# Buck_Schematic.net
KiCad netlist of a schematic drawn in Altium Designer
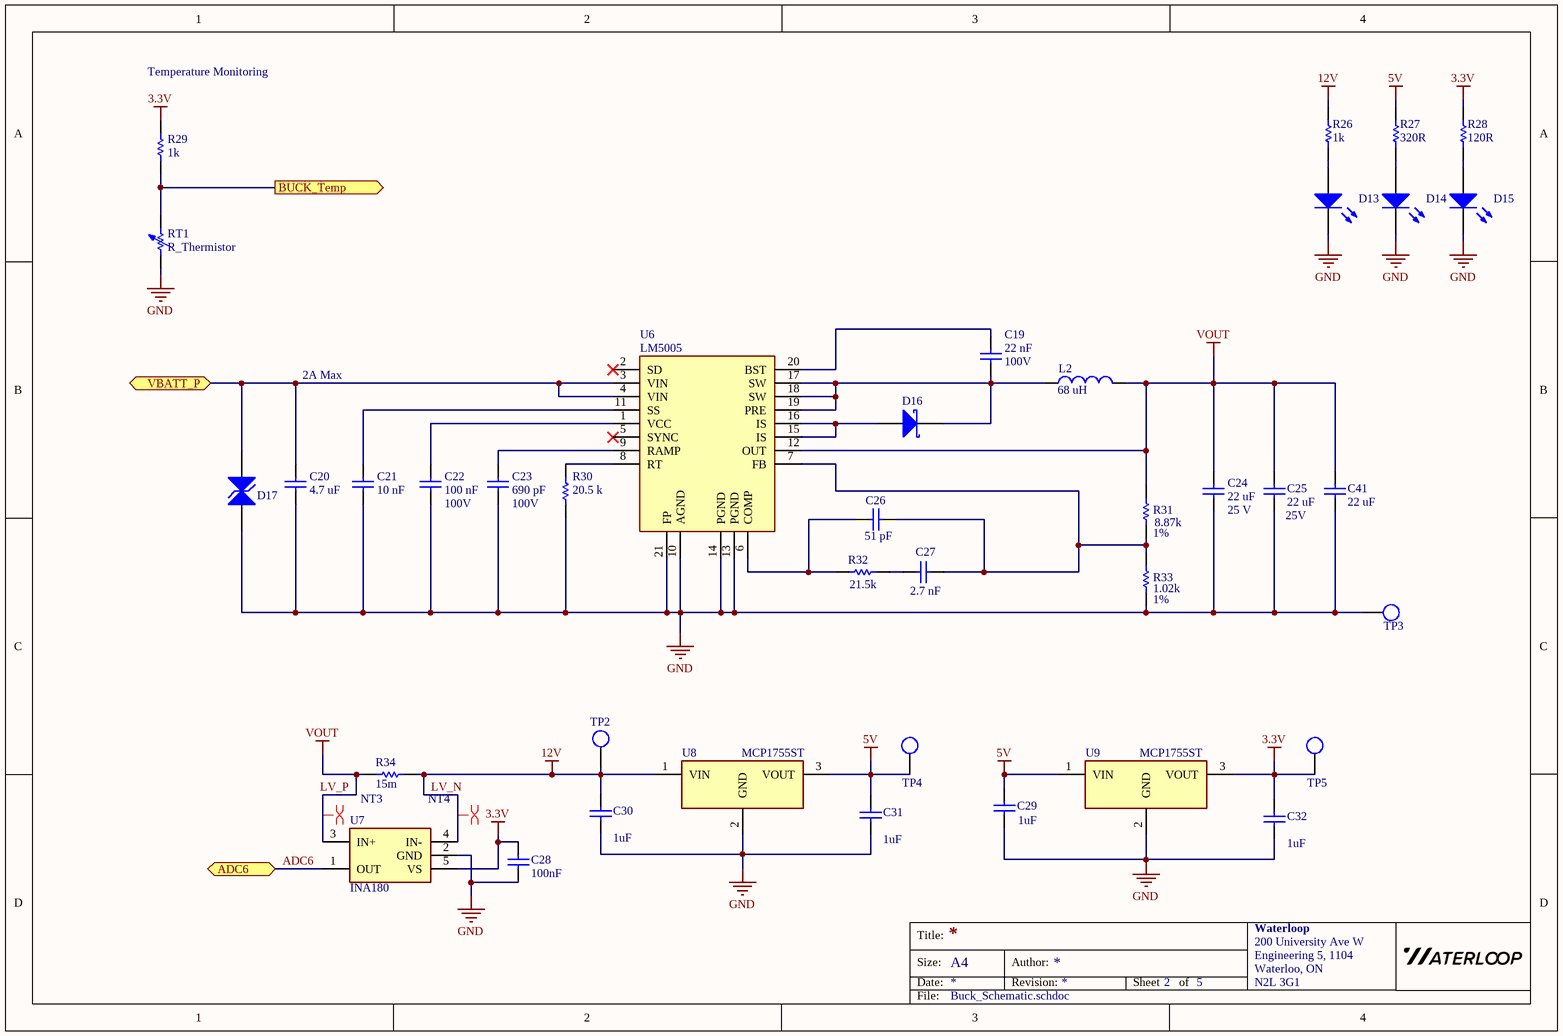
[diagram p0: Buck_Schematic.schdoc]

(export (version "E")
  (design (tool "Eeschema 10.0.6"))
  (components
    (comp (ref "C19")
      (value "22 nF")
      (footprint "0805 - Capacitor")
      (description "CC0805MRX7R0BB223, 0.022 µF± 20% 100V Ceramic Capacitor X7R 0805 (2012 Metric)")
      (fields
        (field (name "MANUFACTURER") "YAGEO")
        (field (name "MANUFACTURER PART NUMBER") "CC0805MRX7R0BB223")
      )
      (libsource (lib "General") (part "Capacitor - Nonpolarized"))
    )
    (comp (ref "C20")
      (value "4.7 uF")
      (footprint "1210 - Capacitor")
      (description "C3225X7S2A475M200AB, CAP CER 4.7UF 100V X7S 1210")
      (fields
        (field (name "MANUFACTURER") "TDK Corporation")
        (field (name "MANUFACTURER PART NUMBER") "C3225X7S2A475M200AB")
      )
      (libsource (lib "General") (part "Capacitor - Nonpolarized"))
    )
    (comp (ref "C21")
      (value "10 nF")
      (footprint "0805 - Capacitor")
      (description "CC0805KRX7R0BB103, 10000 pF ±10% 100V Ceramic Capacitor X7R 0805 (2012 Metric)")
      (fields
        (field (name "MANUFACTURER") "YAGEO")
        (field (name "MANUFACTURER PART NUMBER") "CC0805KRX7R0BB103")
      )
      (libsource (lib "General") (part "Capacitor - Nonpolarized"))
    )
    (comp (ref "C22")
      (value "100 nF")
      (footprint "0805 - Capacitor")
      (description "CC0805KKX7R0BB104, 0.1uF ± 10% 100V Ceramic Capacitor X7R 0805 (2012 Metric)")
      (fields
        (field (name "MANUFACTURER") "YAGEO")
        (field (name "MANUFACTURER PART NUMBER") "CC0805KKX7R0BB104")
      )
      (libsource (lib "General") (part "Capacitor - Nonpolarized"))
    )
    (comp (ref "C23")
      (value "690 pF")
      (footprint "0805 - Capacitor")
      (description "CC0805KRX7R0BB681, 680 pF ± 10% 100V Ceramic Capacitor X7R 0805 (2012 Metric)")
      (fields
        (field (name "MANUFACTURER") "YAGEO")
        (field (name "MANUFACTURER PART NUMBER") "CC0805KRX7R0BB681")
      )
      (libsource (lib "General") (part "Capacitor - Nonpolarized"))
    )
    (comp (ref "C24")
      (value "22 uF")
      (footprint "1210 - Capacitor")
      (description "CC0805ZKY5V6BB226, CAP CER 22UF 10V Y5V 0805")
      (fields
        (field (name "MANUFACTURER") "KYOCERA AVX")
        (field (name "MANUFACTURER PART NUMBER") "12103D226MAT2A")
      )
      (libsource (lib "General") (part "Capacitor - Nonpolarized"))
    )
    (comp (ref "C25")
      (value "22 uF")
      (footprint "1210 - Capacitor")
      (description "EEE-FK1A220R, CAP ALUM 22UF 20% 10V SMD")
      (fields
        (field (name "MANUFACTURER") "KYOCERA AVX")
        (field (name "MANUFACTURER PART NUMBER") "12103D226MAT2A")
      )
      (libsource (lib "General") (part "Capacitor - Nonpolarized"))
    )
    (comp (ref "C26")
      (value "51 pF")
      (footprint "0805 - Capacitor")
      (description "CL21C510JBANNNC,  51 pF ± 5% 50V Ceramic Capacitor C0G NP0 0805 (2012 Metric)")
      (fields
        (field (name "MANUFACTURER") "Samsung Electro-Mechanics")
        (field (name "MANUFACTURER PART NUMBER") "CL21C510JBANNNC")
      )
      (libsource (lib "General") (part "Capacitor - Nonpolarized"))
    )
    (comp (ref "C27")
      (value "2.7 nF")
      (footprint "0805 - Capacitor")
      (description "CC0805KRX7R9BB272, 2700 pF ±10% 50V Ceramic Capacitor X7R 0805 (2012 Metric)")
      (fields
        (field (name "MANUFACTURER") "YAGEO")
        (field (name "MANUFACTURER PART NUMBER") "CC0805KRX7R9BB272")
      )
      (libsource (lib "General") (part "Capacitor - Nonpolarized"))
    )
    (comp (ref "C28")
      (value "100nF")
      (footprint "0805 - Capacitor")
      (description "CC0805KRX7R9BB104, 0.1 µF  \r\n±10% 50V Ceramic Capacitor X7R 0805 (2012 Metric)")
      (fields
        (field (name "MANUFACTURER") "YAGEO")
        (field (name "MANUFACTURER PART NUMBER") "CC0805KRX7R9BB104")
      )
      (libsource (lib "General") (part "Capacitor - Nonpolarized"))
    )
    (comp (ref "C29")
      (value "1uF")
      (footprint "0805 - Capacitor")
      (description "Nonpolarized Capacitor")
      (fields
        (field (name "MANUFACTURER") "YAGEO")
        (field (name "MANUFACTURER PART NUMBER") "CC0805KKX5R8BB105")
      )
      (libsource (lib "General") (part "Capacitor - Nonpolarized"))
    )
    (comp (ref "C30")
      (value "1uF")
      (footprint "0805 - Capacitor")
      (description "Nonpolarized Capacitor")
      (fields
        (field (name "MANUFACTURER") "YAGEO")
        (field (name "MANUFACTURER PART NUMBER") "CC0805KKX5R8BB105")
      )
      (libsource (lib "General") (part "Capacitor - Nonpolarized"))
    )
    (comp (ref "C31")
      (value "1uF")
      (footprint "0805 - Capacitor")
      (description "Nonpolarized Capacitor")
      (fields
        (field (name "MANUFACTURER") "YAGEO")
        (field (name "MANUFACTURER PART NUMBER") "CC0805KKX5R8BB105")
      )
      (libsource (lib "General") (part "Capacitor - Nonpolarized"))
    )
    (comp (ref "C32")
      (value "1uF")
      (footprint "0805 - Capacitor")
      (description "Nonpolarized Capacitor")
      (fields
        (field (name "MANUFACTURER") "YAGEO")
        (field (name "MANUFACTURER PART NUMBER") "CC0805KKX5R8BB105")
      )
      (libsource (lib "General") (part "Capacitor - Nonpolarized"))
    )
    (comp (ref "C41")
      (value "22 uF")
      (footprint "1210 - Capacitor")
      (description "EEE-FK1A220R, CAP ALUM 22UF 20% 10V SMD")
      (fields
        (field (name "MANUFACTURER") "KYOCERA AVX")
        (field (name "MANUFACTURER PART NUMBER") "12103D226MAT2A")
      )
      (libsource (lib "General") (part "Capacitor - Nonpolarized"))
    )
    (comp (ref "D13")
      (value "LED")
      (footprint "0805 - Resistor")
      (description "150080SS75000, LED RED CLEAR 0805 SMD")
      (fields
        (field (name "MANUFACTURER PART NUMBER") "150080SS75000")
        (field (name "MANUFACTURER") "Würth Elektronik")
      )
      (libsource (lib "General") (part "LED"))
    )
    (comp (ref "D14")
      (value "LED")
      (footprint "0805 - Resistor")
      (description "150080SS75000, LED RED CLEAR 0805 SMD")
      (fields
        (field (name "MANUFACTURER PART NUMBER") "150080SS75000")
        (field (name "MANUFACTURER") "Würth Elektronik")
      )
      (libsource (lib "General") (part "LED"))
    )
    (comp (ref "D15")
      (value "LED")
      (footprint "0805 - Resistor")
      (description "150080SS75000, LED RED CLEAR 0805 SMD")
      (fields
        (field (name "MANUFACTURER PART NUMBER") "150080SS75000")
        (field (name "MANUFACTURER") "Würth Elektronik")
      )
      (libsource (lib "General") (part "LED"))
    )
    (comp (ref "D16")
      (value "Diode - Schottky")
      (footprint "SMA - DIODE")
      (description "SK220ATR, 200V 2A SMA")
      (fields
        (field (name "MANUFACTURER") "SMC Diode Solutions")
        (field (name "MANUFACTURER PART NUMBER") "SK220ATR")
      )
      (libsource (lib "General") (part "Diode - Schottky"))
    )
    (comp (ref "D17")
      (value "TVS")
      (footprint "SMB - DIODE")
      (description "TVS Diode")
      (fields (field (name "MANUFACTURER PART NUMBER") "824521601") (field (name "MANUFACTURER") "Wurth"))
      (libsource (lib "General") (part "TVS"))
    )
    (comp (ref "L2")
      (value "68 uH")
      (footprint "MSS1210 - INDUCTOR")
      (description "MSS1210-683MEB, 68 uH ± 20% 4.3 A Ferrite")
      (fields
        (field (name "MANUFACTURER PART NUMBER") "MSS1210-683MEB")
        (field (name "MANUFACTURER") "Coilcraft")
      )
      (libsource (lib "General") (part "Inductor"))
    )
    (comp (ref "NT3") (value "NetTie") (footprint "Net Tie") (libsource (lib "General") (part "Net Tie")))
    (comp (ref "NT4") (value "NetTie") (footprint "Net Tie") (libsource (lib "General") (part "Net Tie")))
    (comp (ref "R26")
      (value "1k")
      (footprint "0603 - Resistor")
      (description "RC0603FR-07510RL, RES 510 OHM 1% 1/10W 0603")
      (fields
        (field (name "MANUFACTURER PART NUMBER") "RC0603JR-071KL")
        (field (name "MANUFACTURER") "YAGEO")
      )
      (libsource (lib "General") (part "Resistor"))
    )
    (comp (ref "R27")
      (value "320R")
      (footprint "0603 - Resistor")
      (description "RC0603FR-07510RL, RES 510 OHM 1% 1/10W 0603")
      (fields
        (field (name "MANUFACTURER PART NUMBER") "RC0603FR-07330RL")
        (field (name "MANUFACTURER") "YAGEO")
      )
      (libsource (lib "General") (part "Resistor"))
    )
    (comp (ref "R28")
      (value "120R")
      (footprint "0603 - Resistor")
      (description "RC0603FR-07510RL, RES 510 OHM 1% 1/10W 0603")
      (fields
        (field (name "MANUFACTURER PART NUMBER") "RC0603FR-10120RL")
        (field (name "MANUFACTURER") "YAGEO")
      )
      (libsource (lib "General") (part "Resistor"))
    )
    (comp (ref "R29")
      (value "1k")
      (footprint "0603 - Resistor")
      (description "RC0603FR-071KL, 1 kOhms ±1% 0.1W Thick Film 0603 (1608 Metric)")
      (fields
        (field (name "MANUFACTURER PART NUMBER") "RC0603JR-071KL")
        (field (name "MANUFACTURER") "YAGEO")
      )
      (libsource (lib "General") (part "Resistor"))
    )
    (comp (ref "R30")
      (value "20.5 k")
      (footprint "0603 - Resistor")
      (description "CRCW060320K5FKEA, 20.5 kOhms ± 1%, 0.1W Thick Film 0603 (1608 Metric)")
      (fields
        (field (name "MANUFACTURER PART NUMBER") "CRCW060320K5FKEA")
        (field (name "MANUFACTURER") "Vishay Dale")
      )
      (libsource (lib "General") (part "Resistor"))
    )
    (comp (ref "R31")
      (value "8.87k")
      (footprint "0805 - Resistor")
      (description "ERJ-6ENF8871V, 8.87 kOhms ±1% 0.125W Thick Film 0805 (2012 Metric)")
      (fields
        (field (name "MANUFACTURER PART NUMBER") "ERJ-6ENF8871V")
        (field (name "MANUFACTURER") "Panasonic Electronic Components")
      )
      (libsource (lib "General") (part "Resistor"))
    )
    (comp (ref "R32")
      (value "21.5k")
      (footprint "0603 - Resistor")
      (description "CRCW060321K5FKEA, 21.5 kOhms  \r\n±1% 0.1W Thick Film 0603 (1608 Metric)")
      (fields
        (field (name "MANUFACTURER PART NUMBER") "CRCW060321K5FKEA")
        (field (name "MANUFACTURER") "Vishay Dale")
      )
      (libsource (lib "General") (part "Resistor"))
    )
    (comp (ref "R33")
      (value "1.02k")
      (footprint "0805 - Resistor")
      (description "ERJ-6ENF1021V, 1.02 kOhms ±1% 0.125W Thick Film 0805 (2012 Metric)")
      (fields
        (field (name "MANUFACTURER PART NUMBER") "ERJ-6ENF1021V")
        (field (name "MANUFACTURER") "Panasonic Electronic Components")
      )
      (libsource (lib "General") (part "Resistor"))
    )
    (comp (ref "R34")
      (value "15m")
      (footprint "0805 - Resistor")
      (description "Resistor")
      (fields
        (field (name "MANUFACTURER PART NUMBER") "ERJ-6CWDR015V")
        (field (name "MANUFACTURER") "Panasonic")
      )
      (libsource (lib "General") (part "Resistor"))
    )
    (comp (ref "RT1")
      (value "R_Thermistor")
      (footprint "0603 - Resistor")
      (description "ERT-J1VR103J, THERMISTOR NTC 10KOHM 4250K 0603")
      (fields
        (field (name "MANUFACTURER PART NUMBER") "ERT-J1VR103J")
        (field (name "MANUFACTURER") "Panasonic Electronic Components")
      )
      (libsource (lib "General") (part "Resistor - Variable"))
    )
    (comp (ref "TP2")
      (value "~")
      (footprint "Test Point - 5002")
      (description "Test Point")
      (libsource (lib "General") (part "Test Point"))
    )
    (comp (ref "TP3")
      (value "~")
      (footprint "Test Point - 5002")
      (description "Test Point")
      (libsource (lib "General") (part "Test Point"))
    )
    (comp (ref "TP4")
      (value "~")
      (footprint "Test Point - 5002")
      (description "Test Point")
      (libsource (lib "General") (part "Test Point"))
    )
    (comp (ref "TP5")
      (value "~")
      (footprint "Test Point - 5002")
      (description "Test Point")
      (libsource (lib "General") (part "Test Point"))
    )
    (comp (ref "U6")
      (value "LM5005")
      (footprint "LM5005")
      (description "7V to 75V 2.5A, Buck Converter")
      (fields
        (field (name "MANUFACTURER") "Texas Instruments")
        (field (name "MANUFACTURER PART NUMBER") "LM5005MHX/NOPB")
      )
      (libsource (lib "GeneralComponents") (part "LM5005"))
    )
    (comp (ref "U7")
      (value "INA180")
      (footprint "INA180")
      (description "0V to 26V Current Sense Amplifier")
      (fields
        (field (name "MANUFACTURER") "Texas Instruments")
        (field (name "MANUFACTURER PART NUMBER") "INA180A3QDBVRQ1")
      )
      (libsource (lib "GeneralComponents") (part "INA180"))
    )
    (comp (ref "U8")
      (value "MCP1755ST")
      (footprint "MCP1755ST")
      (description "Linear Regulator 300mA")
      (fields (field (name "MANUFACTURER") "Microchip"))
      (libsource (lib "GeneralComponents") (part "MCP1755ST"))
    )
    (comp (ref "U9")
      (value "MCP1755ST")
      (footprint "MCP1755ST")
      (description "Linear Regulator 300mA")
      (fields (field (name "MANUFACTURER") "Microchip"))
      (libsource (lib "GeneralComponents") (part "MCP1755ST"))
    )
  )
  (nets
    (net (code "1") (name "/ADC6") (class "Default")
      (node (ref "U7") (pin "1") (pinfunction "OUT_1") (pintype "passive"))
    )
    (net (code "2") (name "/BUCK_Temp") (class "Default")
      (node (ref "R29") (pin "1") (pinfunction "1_1") (pintype "passive"))
      (node (ref "RT1") (pin "2") (pinfunction "2_2") (pintype "passive"))
    )
    (net (code "3") (name "/LV_N") (class "Default")
      (node (ref "NT4") (pin "2") (pinfunction "2_2") (pintype "passive"))
      (node (ref "U7") (pin "4") (pinfunction "IN-_4") (pintype "passive"))
    )
    (net (code "4") (name "/LV_P") (class "Default")
      (node (ref "NT3") (pin "2") (pinfunction "2_2") (pintype "passive"))
      (node (ref "U7") (pin "3") (pinfunction "IN+_3") (pintype "passive"))
    )
    (net (code "5") (name "/VBATT_P") (class "Default")
      (node (ref "C20") (pin "2") (pinfunction "2_2") (pintype "passive"))
      (node (ref "D17") (pin "2") (pinfunction "K_2") (pintype "passive"))
      (node (ref "U6") (pin "3") (pinfunction "VIN_3") (pintype "passive"))
      (node (ref "U6") (pin "4") (pinfunction "VIN_4") (pintype "passive"))
    )
    (net (code "6") (name "3.3V") (class "Default")
      (node (ref "C28") (pin "2") (pinfunction "2_2") (pintype "passive"))
      (node (ref "C32") (pin "1") (pinfunction "1_1") (pintype "passive"))
      (node (ref "R28") (pin "1") (pinfunction "1_1") (pintype "passive"))
      (node (ref "R29") (pin "2") (pinfunction "2_2") (pintype "passive"))
      (node (ref "TP5") (pin "1") (pinfunction "0_1") (pintype "passive"))
      (node (ref "U7") (pin "5") (pinfunction "VS_5") (pintype "passive"))
      (node (ref "U9") (pin "3") (pinfunction "VOUT_3") (pintype "passive"))
    )
    (net (code "7") (name "5V") (class "Default")
      (node (ref "C29") (pin "1") (pinfunction "1_1") (pintype "passive"))
      (node (ref "C31") (pin "1") (pinfunction "1_1") (pintype "passive"))
      (node (ref "R27") (pin "1") (pinfunction "1_1") (pintype "passive"))
      (node (ref "TP4") (pin "1") (pinfunction "0_1") (pintype "passive"))
      (node (ref "U8") (pin "3") (pinfunction "VOUT_3") (pintype "passive"))
      (node (ref "U9") (pin "1") (pinfunction "VIN_1") (pintype "passive"))
    )
    (net (code "8") (name "12V") (class "Default")
      (node (ref "C30") (pin "1") (pinfunction "1_1") (pintype "passive"))
      (node (ref "NT4") (pin "1") (pinfunction "1_1") (pintype "passive"))
      (node (ref "R26") (pin "1") (pinfunction "1_1") (pintype "passive"))
      (node (ref "R34") (pin "1") (pinfunction "1_1") (pintype "passive"))
      (node (ref "TP2") (pin "1") (pinfunction "0_1") (pintype "passive"))
      (node (ref "U8") (pin "1") (pinfunction "VIN_1") (pintype "passive"))
    )
    (net (code "9") (name "GND") (class "Default")
      (node (ref "C20") (pin "1") (pinfunction "1_1") (pintype "passive"))
      (node (ref "C21") (pin "1") (pinfunction "1_1") (pintype "passive"))
      (node (ref "C22") (pin "1") (pinfunction "1_1") (pintype "passive"))
      (node (ref "C23") (pin "1") (pinfunction "1_1") (pintype "passive"))
      (node (ref "C24") (pin "2") (pinfunction "2_2") (pintype "passive"))
      (node (ref "C25") (pin "1") (pinfunction "1_1") (pintype "passive"))
      (node (ref "C28") (pin "1") (pinfunction "1_1") (pintype "passive"))
      (node (ref "C29") (pin "2") (pinfunction "2_2") (pintype "passive"))
      (node (ref "C30") (pin "2") (pinfunction "2_2") (pintype "passive"))
      (node (ref "C31") (pin "2") (pinfunction "2_2") (pintype "passive"))
      (node (ref "C32") (pin "2") (pinfunction "2_2") (pintype "passive"))
      (node (ref "C41") (pin "1") (pinfunction "1_1") (pintype "passive"))
      (node (ref "D13") (pin "2") (pinfunction "K_2") (pintype "passive"))
      (node (ref "D14") (pin "2") (pinfunction "K_2") (pintype "passive"))
      (node (ref "D15") (pin "2") (pinfunction "K_2") (pintype "passive"))
      (node (ref "D17") (pin "1") (pinfunction "A_1") (pintype "passive"))
      (node (ref "R30") (pin "1") (pinfunction "1_1") (pintype "passive"))
      (node (ref "R33") (pin "1") (pinfunction "1_1") (pintype "passive"))
      (node (ref "RT1") (pin "1") (pinfunction "1_1") (pintype "passive"))
      (node (ref "TP3") (pin "1") (pinfunction "0_1") (pintype "passive"))
      (node (ref "U6") (pin "10") (pinfunction "AGND_10") (pintype "passive"))
      (node (ref "U6") (pin "13") (pinfunction "PGND_13") (pintype "passive"))
      (node (ref "U6") (pin "14") (pinfunction "PGND_14") (pintype "passive"))
      (node (ref "U6") (pin "21") (pinfunction "FP_21") (pintype "passive"))
      (node (ref "U7") (pin "2") (pinfunction "GND_2") (pintype "passive"))
      (node (ref "U8") (pin "2") (pinfunction "GND_2") (pintype "passive"))
      (node (ref "U9") (pin "2") (pinfunction "GND_2") (pintype "passive"))
    )
    (net (code "10") (name "Net-(C27-Pad2)") (class "Default")
      (node (ref "C27") (pin "2") (pinfunction "2_2") (pintype "passive"))
      (node (ref "R32") (pin "1") (pinfunction "1_1") (pintype "passive"))
    )
    (net (code "11") (name "Net-(D13-A)") (class "Default")
      (node (ref "D13") (pin "1") (pinfunction "A_1") (pintype "passive"))
      (node (ref "R26") (pin "2") (pinfunction "2_2") (pintype "passive"))
    )
    (net (code "12") (name "Net-(D14-A)") (class "Default")
      (node (ref "D14") (pin "1") (pinfunction "A_1") (pintype "passive"))
      (node (ref "R27") (pin "2") (pinfunction "2_2") (pintype "passive"))
    )
    (net (code "13") (name "Net-(D15-A)") (class "Default")
      (node (ref "D15") (pin "1") (pinfunction "A_1") (pintype "passive"))
      (node (ref "R28") (pin "2") (pinfunction "2_2") (pintype "passive"))
    )
    (net (code "14") (name "Net-(D16-A)") (class "Default")
      (node (ref "D16") (pin "1") (pinfunction "A_1") (pintype "passive"))
      (node (ref "U6") (pin "15") (pinfunction "IS_15") (pintype "passive"))
      (node (ref "U6") (pin "16") (pinfunction "IS_16") (pintype "passive"))
    )
    (net (code "15") (name "Net-(D16-K)") (class "Default")
      (node (ref "C19") (pin "1") (pinfunction "1_1") (pintype "passive"))
      (node (ref "D16") (pin "2") (pinfunction "K_2") (pintype "passive"))
      (node (ref "L2") (pin "1") (pinfunction "1_1") (pintype "passive"))
      (node (ref "U6") (pin "17") (pinfunction "SW_17") (pintype "passive"))
      (node (ref "U6") (pin "18") (pinfunction "SW_18") (pintype "passive"))
      (node (ref "U6") (pin "19") (pinfunction "PRE_19") (pintype "passive"))
    )
    (net (code "16") (name "Net-(U6-BST)") (class "Default")
      (node (ref "C19") (pin "2") (pinfunction "2_2") (pintype "passive"))
      (node (ref "U6") (pin "20") (pinfunction "BST_20") (pintype "passive"))
    )
    (net (code "17") (name "Net-(U6-COMP)") (class "Default")
      (node (ref "C26") (pin "2") (pinfunction "2_2") (pintype "passive"))
      (node (ref "R32") (pin "2") (pinfunction "2_2") (pintype "passive"))
      (node (ref "U6") (pin "6") (pinfunction "COMP_6") (pintype "passive"))
    )
    (net (code "18") (name "Net-(U6-FB)") (class "Default")
      (node (ref "C26") (pin "1") (pinfunction "1_1") (pintype "passive"))
      (node (ref "C27") (pin "1") (pinfunction "1_1") (pintype "passive"))
      (node (ref "R31") (pin "1") (pinfunction "1_1") (pintype "passive"))
      (node (ref "R33") (pin "2") (pinfunction "2_2") (pintype "passive"))
      (node (ref "U6") (pin "7") (pinfunction "FB_7") (pintype "passive"))
    )
    (net (code "19") (name "Net-(U6-RAMP)") (class "Default")
      (node (ref "C23") (pin "2") (pinfunction "2_2") (pintype "passive"))
      (node (ref "U6") (pin "9") (pinfunction "RAMP_9") (pintype "passive"))
    )
    (net (code "20") (name "Net-(U6-RT)") (class "Default")
      (node (ref "R30") (pin "2") (pinfunction "2_2") (pintype "passive"))
      (node (ref "U6") (pin "8") (pinfunction "RT_8") (pintype "passive"))
    )
    (net (code "21") (name "Net-(U6-SS)") (class "Default")
      (node (ref "C21") (pin "2") (pinfunction "2_2") (pintype "passive"))
      (node (ref "U6") (pin "11") (pinfunction "SS_11") (pintype "passive"))
    )
    (net (code "22") (name "Net-(U6-VCC)") (class "Default")
      (node (ref "C22") (pin "2") (pinfunction "2_2") (pintype "passive"))
      (node (ref "U6") (pin "1") (pinfunction "VCC_1") (pintype "passive"))
    )
    (net (code "23") (name "VOUT") (class "Default")
      (node (ref "C24") (pin "1") (pinfunction "1_1") (pintype "passive"))
      (node (ref "C25") (pin "2") (pinfunction "2_2") (pintype "passive"))
      (node (ref "C41") (pin "2") (pinfunction "2_2") (pintype "passive"))
      (node (ref "L2") (pin "2") (pinfunction "2_2") (pintype "passive"))
      (node (ref "NT3") (pin "1") (pinfunction "1_1") (pintype "passive"))
      (node (ref "R31") (pin "2") (pinfunction "2_2") (pintype "passive"))
      (node (ref "R34") (pin "2") (pinfunction "2_2") (pintype "passive"))
      (node (ref "U6") (pin "12") (pinfunction "OUT_12") (pintype "passive"))
    )
    (net (code "24") (name "unconnected-(U6-SD-Pad2)") (class "Default")
      (node (ref "U6") (pin "2") (pinfunction "SD_2") (pintype "passive+no_connect"))
    )
    (net (code "25") (name "unconnected-(U6-SYNC-Pad5)") (class "Default")
      (node (ref "U6") (pin "5") (pinfunction "SYNC_5") (pintype "passive+no_connect"))
    )
  )
)
